# EPGinputDB.net
KiCad netlist of a schematic drawn in EAGLE
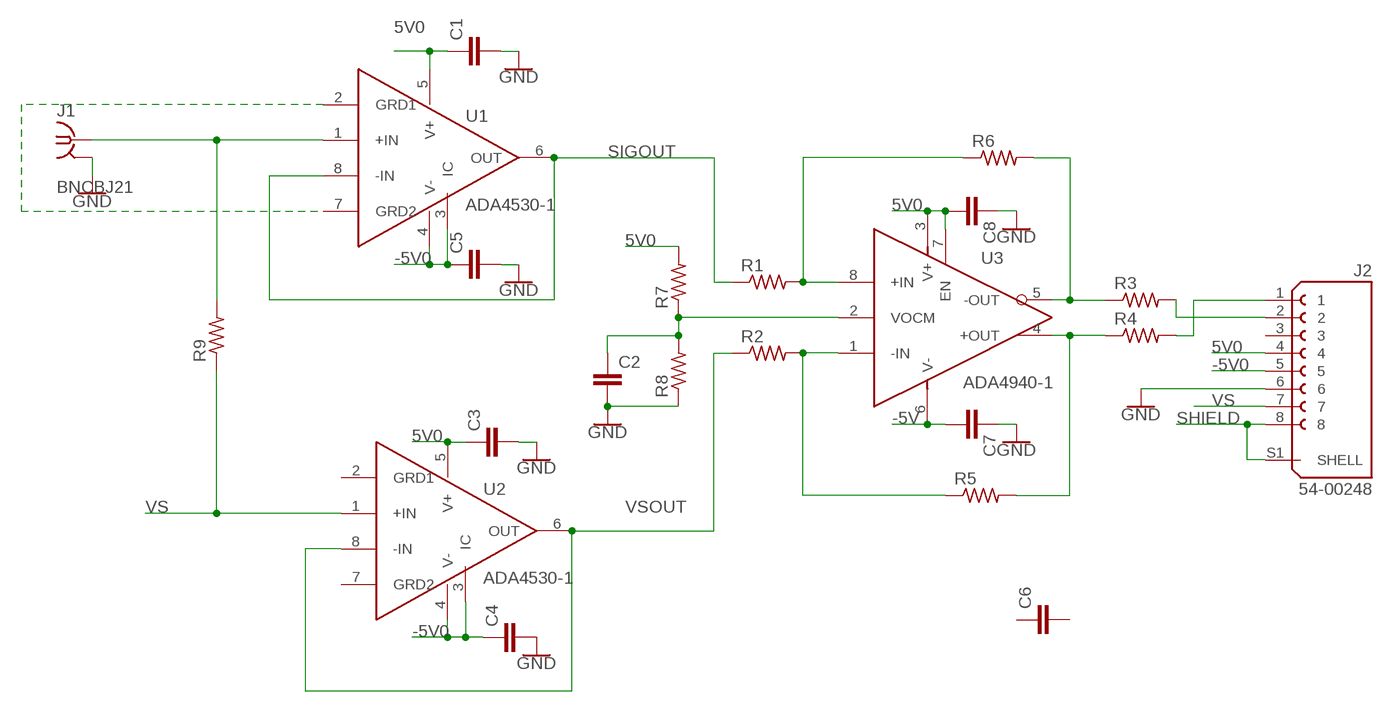
[diagram p0: schematic, sheet 1]

(export (version "E")
  (design (tool "Eeschema 10.0.6"))
  (components
    (comp (ref "C1")
      (value "CAPS0603S")
      (footprint "eagle-import:0603S")
      (libsource (lib "eagle-import") (part "CAPS0603S"))
    )
    (comp (ref "C2")
      (value "CAPS0603S")
      (footprint "eagle-import:0603S")
      (libsource (lib "eagle-import") (part "CAPS0603S"))
    )
    (comp (ref "C3")
      (value "CAPS0603S")
      (footprint "eagle-import:0603S")
      (libsource (lib "eagle-import") (part "CAPS0603S"))
    )
    (comp (ref "C4")
      (value "CAPS0603S")
      (footprint "eagle-import:0603S")
      (libsource (lib "eagle-import") (part "CAPS0603S"))
    )
    (comp (ref "C5")
      (value "CAPS0603S")
      (footprint "eagle-import:0603S")
      (libsource (lib "eagle-import") (part "CAPS0603S"))
    )
    (comp (ref "C6")
      (value "CAPS0603S")
      (footprint "eagle-import:0603S")
      (libsource (lib "eagle-import") (part "CAPS0603S"))
    )
    (comp (ref "C7")
      (value "CAPS0603S")
      (footprint "eagle-import:0603S")
      (libsource (lib "eagle-import") (part "CAPS0603S"))
    )
    (comp (ref "C8")
      (value "CAPS0603S")
      (footprint "eagle-import:0603S")
      (libsource (lib "eagle-import") (part "CAPS0603S"))
    )
    (comp (ref "J1")
      (value "BNCBJ21")
      (footprint "eagle-import:BNC-BJ21")
      (libsource (lib "eagle-import") (part "BNCBJ21"))
    )
    (comp (ref "J2")
      (value "54-00248")
      (footprint "eagle-import:TENSILITY_54-00248")
      (fields (field (name "MANUFACTURER") "Tensility"))
      (libsource (lib "eagle-import") (part "54-00248"))
    )
    (comp (ref "R1")
      (value "RESISTOR_SM0805S")
      (footprint "eagle-import:0805S")
      (libsource (lib "eagle-import") (part "RESISTOR_SM0805S"))
    )
    (comp (ref "R2")
      (value "RESISTOR_SM0805S")
      (footprint "eagle-import:0805S")
      (libsource (lib "eagle-import") (part "RESISTOR_SM0805S"))
    )
    (comp (ref "R3")
      (value "RESISTOR_SM0805S")
      (footprint "eagle-import:0805S")
      (libsource (lib "eagle-import") (part "RESISTOR_SM0805S"))
    )
    (comp (ref "R4")
      (value "RESISTOR_SM0805S")
      (footprint "eagle-import:0805S")
      (libsource (lib "eagle-import") (part "RESISTOR_SM0805S"))
    )
    (comp (ref "R5")
      (value "RESISTOR_SM0805S")
      (footprint "eagle-import:0805S")
      (libsource (lib "eagle-import") (part "RESISTOR_SM0805S"))
    )
    (comp (ref "R6")
      (value "RESISTOR_SM0805S")
      (footprint "eagle-import:0805S")
      (libsource (lib "eagle-import") (part "RESISTOR_SM0805S"))
    )
    (comp (ref "R7")
      (value "RESISTOR_SM0805S")
      (footprint "eagle-import:0805S")
      (libsource (lib "eagle-import") (part "RESISTOR_SM0805S"))
    )
    (comp (ref "R8")
      (value "RESISTOR_SM0805S")
      (footprint "eagle-import:0805S")
      (libsource (lib "eagle-import") (part "RESISTOR_SM0805S"))
    )
    (comp (ref "R9")
      (value "R-US_0617/22")
      (footprint "eagle-import:0617_22")
      (libsource (lib "eagle-import") (part "R-US_0617/22"))
    )
    (comp (ref "U1")
      (value "ADA4530-1")
      (footprint "eagle-import:SOIC-8")
      (libsource (lib "eagle-import") (part "ADA4530-1"))
    )
    (comp (ref "U2")
      (value "ADA4530-1")
      (footprint "eagle-import:SOIC-8")
      (libsource (lib "eagle-import") (part "ADA4530-1"))
    )
    (comp (ref "U3")
      (value "ADA4940-1")
      (footprint "eagle-import:SOIC-8")
      (libsource (lib "eagle-import") (part "ADA4940-1"))
    )
  )
  (nets
    (net (code "1") (name "/-5V") (class "Default")
      (node (ref "C7") (pin "2") (pinfunction "2_2") (pintype "passive"))
      (node (ref "U3") (pin "6") (pinfunction "V-_6") (pintype "bidirectional"))
    )
    (net (code "2") (name "/-5V0") (class "Default")
      (node (ref "C4") (pin "1") (pinfunction "1_1") (pintype "passive"))
      (node (ref "C5") (pin "1") (pinfunction "1_1") (pintype "passive"))
      (node (ref "J2") (pin "5") (pinfunction "5_5") (pintype "passive"))
      (node (ref "U1") (pin "3") (pinfunction "IC_3") (pintype "bidirectional"))
      (node (ref "U1") (pin "4") (pinfunction "V-_4") (pintype "bidirectional"))
      (node (ref "U2") (pin "3") (pinfunction "IC_3") (pintype "bidirectional"))
      (node (ref "U2") (pin "4") (pinfunction "V-_4") (pintype "bidirectional"))
    )
    (net (code "3") (name "/5V0") (class "Default")
      (node (ref "C1") (pin "1") (pinfunction "1_1") (pintype "passive"))
      (node (ref "C3") (pin "1") (pinfunction "1_1") (pintype "passive"))
      (node (ref "C8") (pin "2") (pinfunction "2_2") (pintype "passive"))
      (node (ref "J2") (pin "4") (pinfunction "4_4") (pintype "passive"))
      (node (ref "R7") (pin "2") (pinfunction "2_2") (pintype "passive"))
      (node (ref "U1") (pin "5") (pinfunction "V+_5") (pintype "bidirectional"))
      (node (ref "U2") (pin "5") (pinfunction "V+_5") (pintype "bidirectional"))
      (node (ref "U3") (pin "3") (pinfunction "V+_3") (pintype "bidirectional"))
      (node (ref "U3") (pin "7") (pinfunction "EN_7") (pintype "bidirectional"))
    )
    (net (code "4") (name "/SHIELD") (class "Default")
      (node (ref "J2") (pin "8") (pinfunction "8_8") (pintype "passive"))
      (node (ref "J2") (pin "S1") (pinfunction "SHELL_S1") (pintype "passive"))
    )
    (net (code "5") (name "/SIGOUT") (class "Default")
      (node (ref "R1") (pin "1") (pinfunction "1_1") (pintype "passive"))
      (node (ref "U1") (pin "6") (pinfunction "OUT_6") (pintype "bidirectional"))
      (node (ref "U1") (pin "8") (pinfunction "-IN_8") (pintype "bidirectional"))
    )
    (net (code "6") (name "/VS") (class "Default")
      (node (ref "J2") (pin "7") (pinfunction "7_7") (pintype "passive"))
      (node (ref "R9") (pin "1") (pinfunction "1_1") (pintype "passive"))
      (node (ref "U2") (pin "1") (pinfunction "+IN_1") (pintype "bidirectional"))
    )
    (net (code "7") (name "/VSOUT") (class "Default")
      (node (ref "R2") (pin "1") (pinfunction "1_1") (pintype "passive"))
      (node (ref "U2") (pin "6") (pinfunction "OUT_6") (pintype "bidirectional"))
      (node (ref "U2") (pin "8") (pinfunction "-IN_8") (pintype "bidirectional"))
    )
    (net (code "8") (name "GND") (class "Default")
      (node (ref "C1") (pin "2") (pinfunction "2_2") (pintype "passive"))
      (node (ref "C2") (pin "2") (pinfunction "2_2") (pintype "passive"))
      (node (ref "C3") (pin "2") (pinfunction "2_2") (pintype "passive"))
      (node (ref "C4") (pin "2") (pinfunction "2_2") (pintype "passive"))
      (node (ref "C5") (pin "2") (pinfunction "2_2") (pintype "passive"))
      (node (ref "C7") (pin "1") (pinfunction "1_1") (pintype "passive"))
      (node (ref "C8") (pin "1") (pinfunction "1_1") (pintype "passive"))
      (node (ref "J1") (pin "P$1") (pinfunction "GND_P$1") (pintype "passive"))
      (node (ref "J2") (pin "6") (pinfunction "6_6") (pintype "passive"))
      (node (ref "R8") (pin "1") (pinfunction "1_1") (pintype "passive"))
    )
    (net (code "9") (name "Net-(J1-1)") (class "Default")
      (node (ref "J1") (pin "P$2") (pinfunction "1_P$2") (pintype "passive"))
      (node (ref "R9") (pin "2") (pinfunction "2_2") (pintype "passive"))
      (node (ref "U1") (pin "1") (pinfunction "+IN_1") (pintype "bidirectional"))
    )
    (net (code "10") (name "Net-(J2-Pad1)") (class "Default")
      (node (ref "J2") (pin "1") (pinfunction "1_1") (pintype "passive"))
      (node (ref "R4") (pin "2") (pinfunction "2_2") (pintype "passive"))
    )
    (net (code "11") (name "Net-(J2-Pad2)") (class "Default")
      (node (ref "J2") (pin "2") (pinfunction "2_2") (pintype "passive"))
      (node (ref "R3") (pin "2") (pinfunction "2_2") (pintype "passive"))
    )
    (net (code "12") (name "Net-(U1-GRD1)") (class "Default")
      (node (ref "U1") (pin "2") (pinfunction "GRD1_2") (pintype "bidirectional"))
      (node (ref "U1") (pin "7") (pinfunction "GRD2_7") (pintype "bidirectional"))
    )
    (net (code "13") (name "Net-(U3-+IN)") (class "Default")
      (node (ref "R1") (pin "2") (pinfunction "2_2") (pintype "passive"))
      (node (ref "R6") (pin "1") (pinfunction "1_1") (pintype "passive"))
      (node (ref "U3") (pin "8") (pinfunction "+IN_8") (pintype "bidirectional"))
    )
    (net (code "14") (name "Net-(U3-+OUT)") (class "Default")
      (node (ref "R4") (pin "1") (pinfunction "1_1") (pintype "passive"))
      (node (ref "R5") (pin "2") (pinfunction "2_2") (pintype "passive"))
      (node (ref "U3") (pin "4") (pinfunction "+OUT_4") (pintype "bidirectional"))
    )
    (net (code "15") (name "Net-(U3--IN)") (class "Default")
      (node (ref "R2") (pin "2") (pinfunction "2_2") (pintype "passive"))
      (node (ref "R5") (pin "1") (pinfunction "1_1") (pintype "passive"))
      (node (ref "U3") (pin "1") (pinfunction "-IN_1") (pintype "bidirectional"))
    )
    (net (code "16") (name "Net-(U3--OUT)") (class "Default")
      (node (ref "R3") (pin "1") (pinfunction "1_1") (pintype "passive"))
      (node (ref "R6") (pin "2") (pinfunction "2_2") (pintype "passive"))
      (node (ref "U3") (pin "5") (pinfunction "-OUT_5") (pintype "bidirectional"))
    )
    (net (code "17") (name "Net-(U3-VOCM)") (class "Default")
      (node (ref "C2") (pin "1") (pinfunction "1_1") (pintype "passive"))
      (node (ref "R7") (pin "1") (pinfunction "1_1") (pintype "passive"))
      (node (ref "R8") (pin "2") (pinfunction "2_2") (pintype "passive"))
      (node (ref "U3") (pin "2") (pinfunction "VOCM_2") (pintype "bidirectional"))
    )
    (net (code "18") (name "unconnected-(C6-Pad1)") (class "Default")
      (node (ref "C6") (pin "1") (pinfunction "1_1") (pintype "passive"))
    )
    (net (code "19") (name "unconnected-(C6-Pad2)") (class "Default")
      (node (ref "C6") (pin "2") (pinfunction "2_2") (pintype "passive"))
    )
    (net (code "20") (name "unconnected-(J2-Pad3)") (class "Default")
      (node (ref "J2") (pin "3") (pinfunction "3_3") (pintype "passive"))
    )
    (net (code "21") (name "unconnected-(U2-GRD1-Pad2)") (class "Default")
      (node (ref "U2") (pin "2") (pinfunction "GRD1_2") (pintype "bidirectional"))
    )
    (net (code "22") (name "unconnected-(U2-GRD2-Pad7)") (class "Default")
      (node (ref "U2") (pin "7") (pinfunction "GRD2_7") (pintype "bidirectional"))
    )
  )
)
